# FINAL_PROJECT.net
KiCad netlist of a schematic drawn in EAGLE
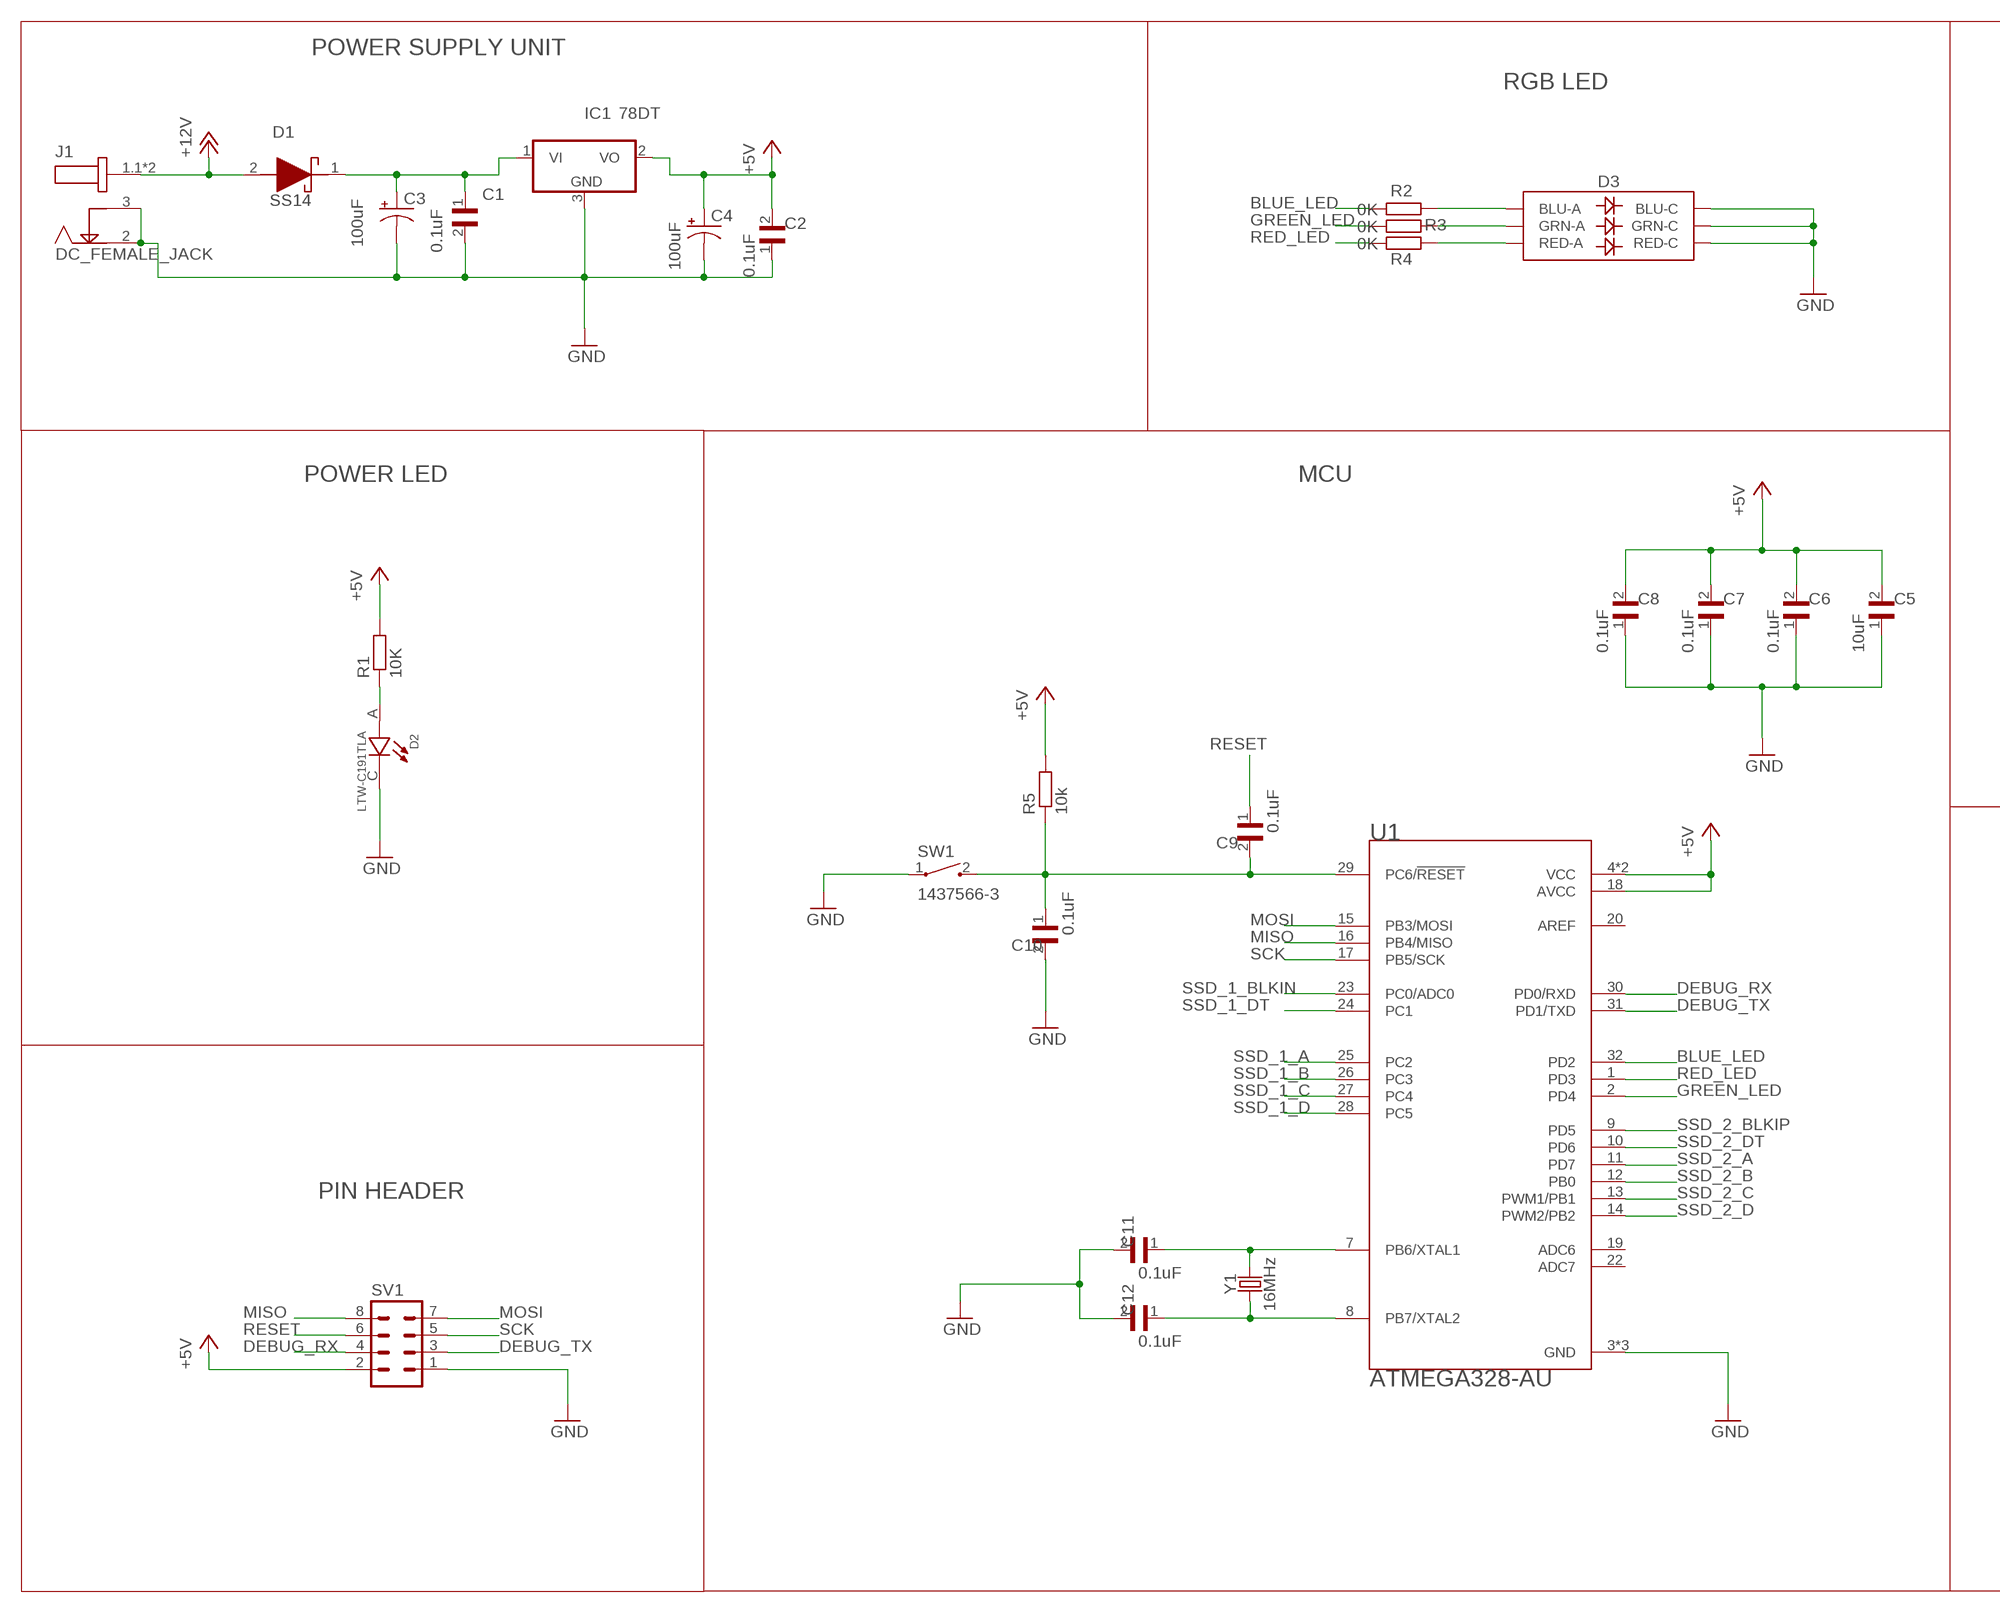
[diagram p0: schematic, sheet 1, part 1 of 2]
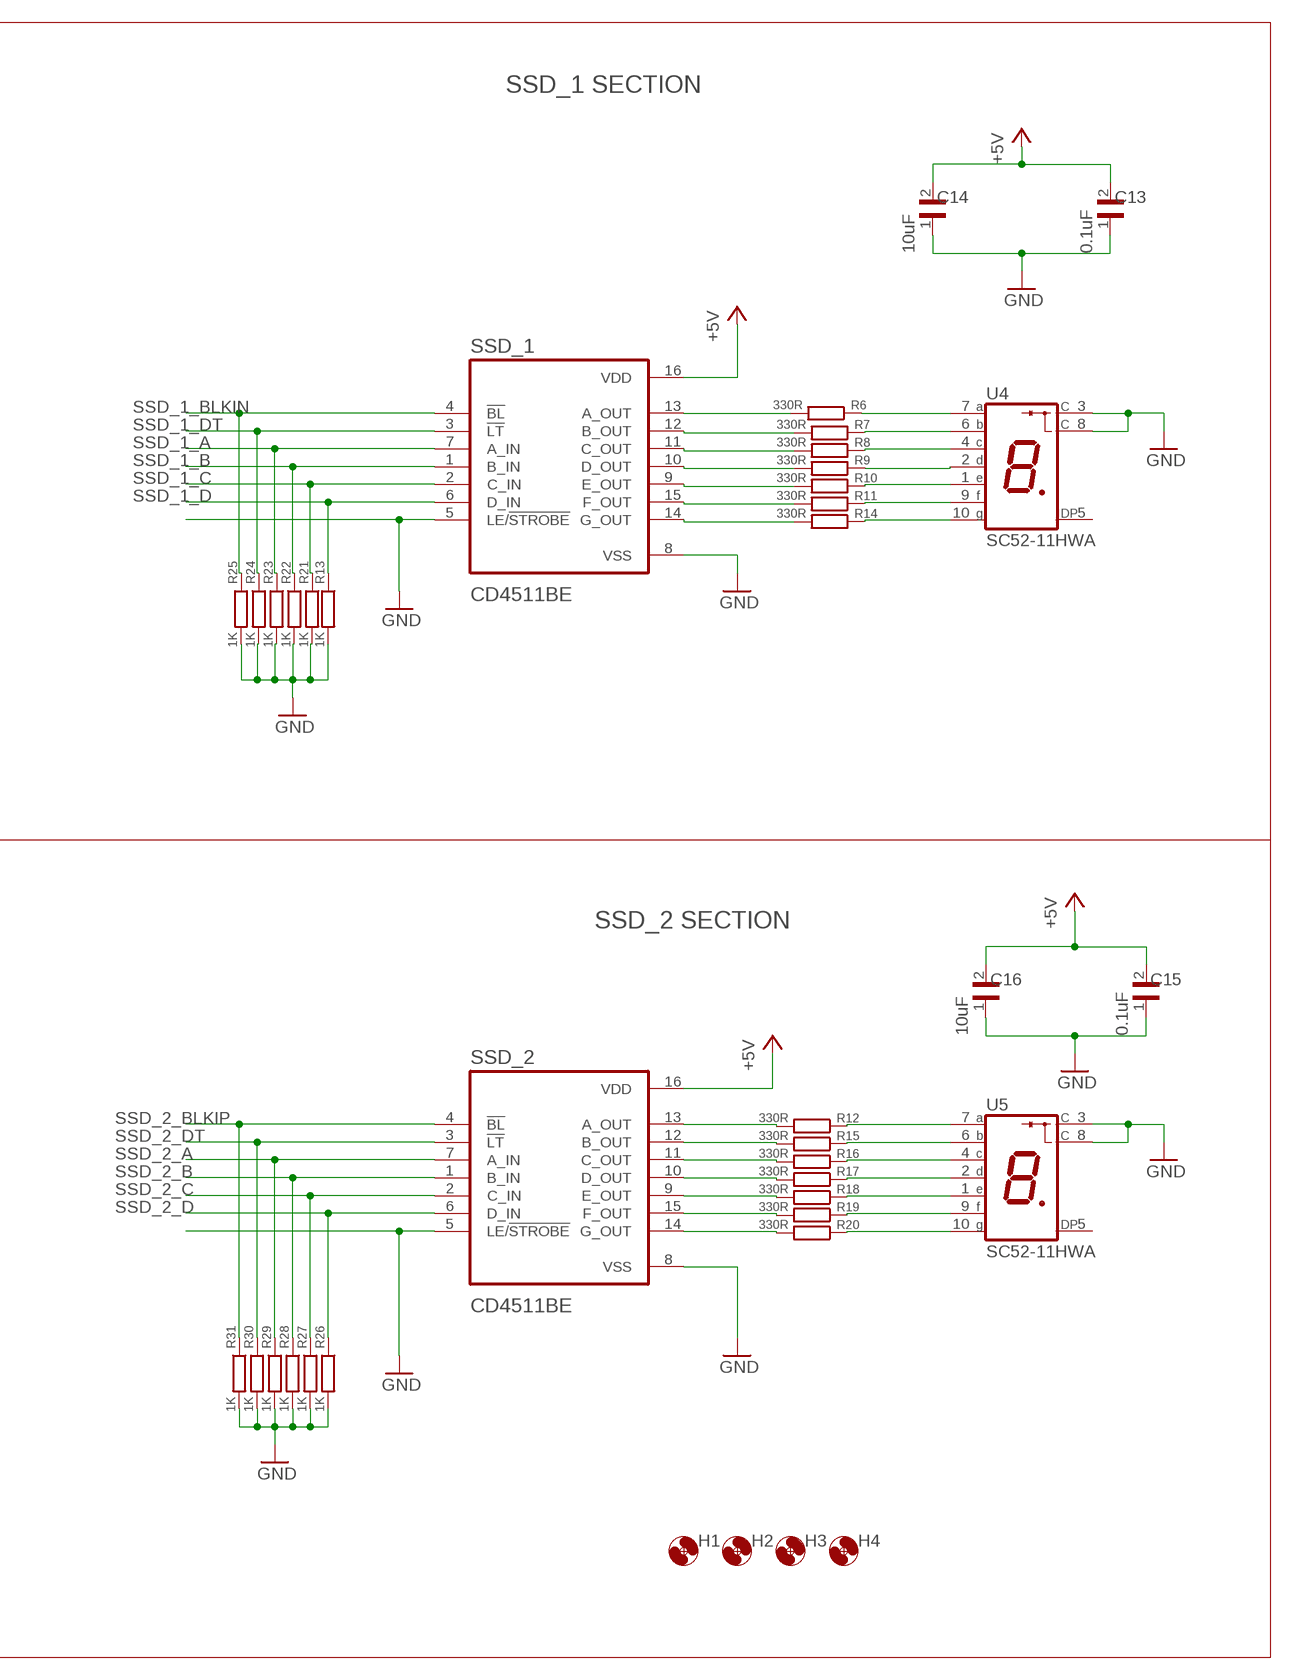
[diagram p1: schematic, sheet 1, part 2 of 2]

(export (version "E")
  (design (tool "Eeschema 10.0.6"))
  (components
    (comp (ref "C1")
      (value "0.1uF")
      (footprint "eagle-import:C0603")
      (fields (field (name "MF") "TDK") (field (name "MP") "CGA3E2X7R1H104K080AA"))
      (libsource (lib "eagle-import") (part "CAPACITOR"))
    )
    (comp (ref "C2")
      (value "0.1uF")
      (footprint "eagle-import:C0603")
      (fields
        (field (name "MF") "TDK")
        (field (name "MP") "CGA3E2X7R1H104K080AA")
        (field (name "SPICEPREFIX") "C")
      )
      (libsource (lib "eagle-import") (part "CAPACITOR"))
    )
    (comp (ref "C3")
      (value "100uF")
      (footprint "eagle-import:CPOL-RADIAL-2.5MM-6.5MM")
      (libsource (lib "eagle-import") (part "100UF-POLAR-RADIAL-2.5MM-25V-20%"))
    )
    (comp (ref "C4")
      (value "100uF")
      (footprint "eagle-import:CPOL-RADIAL-2.5MM-6.5MM")
      (libsource (lib "eagle-import") (part "100UF-POLAR-RADIAL-2.5MM-25V-20%"))
    )
    (comp (ref "C5")
      (value "10uF")
      (footprint "eagle-import:C0603")
      (fields
        (field (name "MF") "TDK")
        (field (name "MP") "CGA3E2X7R1H104K080AA")
        (field (name "SPICEPREFIX") "C")
      )
      (libsource (lib "eagle-import") (part "CAPACITOR"))
    )
    (comp (ref "C6")
      (value "0.1uF")
      (footprint "eagle-import:C0603")
      (fields
        (field (name "MF") "TDK")
        (field (name "MP") "CGA3E2X7R1H104K080AA")
        (field (name "SPICEPREFIX") "C")
      )
      (libsource (lib "eagle-import") (part "CAPACITOR"))
    )
    (comp (ref "C7")
      (value "0.1uF")
      (footprint "eagle-import:C0603")
      (fields
        (field (name "MF") "TDK")
        (field (name "MP") "CGA3E2X7R1H104K080AA")
        (field (name "SPICEPREFIX") "C")
      )
      (libsource (lib "eagle-import") (part "CAPACITOR"))
    )
    (comp (ref "C8")
      (value "0.1uF")
      (footprint "eagle-import:C0603")
      (fields
        (field (name "MF") "TDK")
        (field (name "MP") "CGA3E2X7R1H104K080AA")
        (field (name "SPICEPREFIX") "C")
      )
      (libsource (lib "eagle-import") (part "CAPACITOR"))
    )
    (comp (ref "C9")
      (value "0.1uF")
      (footprint "eagle-import:C0603")
      (fields
        (field (name "MF") "TDK")
        (field (name "MP") "CGA3E2X7R1H104K080AA")
        (field (name "SPICEPREFIX") "C")
      )
      (libsource (lib "eagle-import") (part "CAPACITOR"))
    )
    (comp (ref "C10")
      (value "0.1uF")
      (footprint "eagle-import:C0603")
      (fields
        (field (name "MF") "TDK")
        (field (name "MP") "CGA3E2X7R1H104K080AA")
        (field (name "SPICEPREFIX") "C")
      )
      (libsource (lib "eagle-import") (part "CAPACITOR"))
    )
    (comp (ref "C11")
      (value "0.1uF")
      (footprint "eagle-import:C0603")
      (fields
        (field (name "MF") "TDK")
        (field (name "MP") "CGA3E2X7R1H104K080AA")
        (field (name "SPICEPREFIX") "C")
      )
      (libsource (lib "eagle-import") (part "CAPACITOR"))
    )
    (comp (ref "C12")
      (value "0.1uF")
      (footprint "eagle-import:C0603")
      (fields
        (field (name "MF") "TDK")
        (field (name "MP") "CGA3E2X7R1H104K080AA")
        (field (name "SPICEPREFIX") "C")
      )
      (libsource (lib "eagle-import") (part "CAPACITOR"))
    )
    (comp (ref "C13")
      (value "0.1uF")
      (footprint "eagle-import:C0603")
      (fields
        (field (name "MF") "TDK")
        (field (name "MP") "CGA3E2X7R1H104K080AA")
        (field (name "SPICEPREFIX") "C")
      )
      (libsource (lib "eagle-import") (part "CAPACITOR"))
    )
    (comp (ref "C14")
      (value "10uF")
      (footprint "eagle-import:C0603")
      (fields
        (field (name "MF") "TDK")
        (field (name "MP") "CGA3E2X7R1H104K080AA")
        (field (name "SPICEPREFIX") "C")
      )
      (libsource (lib "eagle-import") (part "CAPACITOR"))
    )
    (comp (ref "C15")
      (value "0.1uF")
      (footprint "eagle-import:C0603")
      (fields
        (field (name "MF") "TDK")
        (field (name "MP") "CGA3E2X7R1H104K080AA")
        (field (name "SPICEPREFIX") "C")
      )
      (libsource (lib "eagle-import") (part "CAPACITOR"))
    )
    (comp (ref "C16")
      (value "10uF")
      (footprint "eagle-import:C0603")
      (fields
        (field (name "MF") "TDK")
        (field (name "MP") "CGA3E2X7R1H104K080AA")
        (field (name "SPICEPREFIX") "C")
      )
      (libsource (lib "eagle-import") (part "CAPACITOR"))
    )
    (comp (ref "D1")
      (value "SS14")
      (footprint "eagle-import:DIOM5126X250N")
      (fields (field (name "MOUSER_PART_NUMBER") "821-SS14"))
      (libsource (lib "eagle-import") (part "SS14"))
    )
    (comp (ref "D2")
      (value "LTW-C191TLA")
      (footprint "eagle-import:LEDC1608X65N")
      (fields (field (name "MF") "Lite-On"))
      (libsource (lib "eagle-import") (part "LTW-C191TLA"))
    )
    (comp (ref "D3")
      (value "LED-RGBNO_IC")
      (footprint "eagle-import:LED-TRICOLOR-5050")
      (libsource (lib "eagle-import") (part "LED-RGBNO_IC"))
    )
    (comp (ref "H1")
      (value "MOUNT-HOLE2.8")
      (footprint "eagle-import:2,8")
      (libsource (lib "eagle-import") (part "MOUNT-HOLE2.8"))
    )
    (comp (ref "H2")
      (value "MOUNT-HOLE2.8")
      (footprint "eagle-import:2,8")
      (libsource (lib "eagle-import") (part "MOUNT-HOLE2.8"))
    )
    (comp (ref "H3")
      (value "MOUNT-HOLE2.8")
      (footprint "eagle-import:2,8")
      (libsource (lib "eagle-import") (part "MOUNT-HOLE2.8"))
    )
    (comp (ref "H4")
      (value "MOUNT-HOLE2.8")
      (footprint "eagle-import:2,8")
      (libsource (lib "eagle-import") (part "MOUNT-HOLE2.8"))
    )
    (comp (ref "IC1")
      (value "78DT")
      (footprint "eagle-import:TO252")
      (libsource (lib "eagle-import") (part "78DT"))
    )
    (comp (ref "J1")
      (value "DC_FEMALE_JACK")
      (footprint "eagle-import:GCT_DCJ200-05-A-XX-X_REVA")
      (fields (field (name "MF") "Global Connector Technology") (field (name "MP") "DCJ200-05-A-K1-A"))
      (libsource (lib "eagle-import") (part "DCJ200-05-A-XX-X_REVA"))
    )
    (comp (ref "R1")
      (value "10K")
      (footprint "eagle-import:R0603")
      (fields (field (name "MF") "Yageo"))
      (libsource (lib "eagle-import") (part "RESISTOR"))
    )
    (comp (ref "R2")
      (value "0K")
      (footprint "eagle-import:R0603")
      (fields (field (name "MF") "Yageo"))
      (libsource (lib "eagle-import") (part "RESISTOR"))
    )
    (comp (ref "R3")
      (value "0K")
      (footprint "eagle-import:R0603")
      (fields (field (name "MF") "Yageo"))
      (libsource (lib "eagle-import") (part "RESISTOR"))
    )
    (comp (ref "R4")
      (value "0K")
      (footprint "eagle-import:R0603")
      (fields (field (name "MF") "Yageo"))
      (libsource (lib "eagle-import") (part "RESISTOR"))
    )
    (comp (ref "R5")
      (value "10k")
      (footprint "eagle-import:R0603")
      (fields (field (name "MF") "Yageo"))
      (libsource (lib "eagle-import") (part "RESISTOR"))
    )
    (comp (ref "R6")
      (value "330R")
      (footprint "eagle-import:R0603")
      (fields (field (name "MF") "Yageo"))
      (libsource (lib "eagle-import") (part "RESISTOR"))
    )
    (comp (ref "R7")
      (value "330R")
      (footprint "eagle-import:R0603")
      (fields (field (name "MF") "Yageo"))
      (libsource (lib "eagle-import") (part "RESISTOR"))
    )
    (comp (ref "R8")
      (value "330R")
      (footprint "eagle-import:R0603")
      (fields (field (name "MF") "Yageo"))
      (libsource (lib "eagle-import") (part "RESISTOR"))
    )
    (comp (ref "R9")
      (value "330R")
      (footprint "eagle-import:R0603")
      (fields (field (name "MF") "Yageo"))
      (libsource (lib "eagle-import") (part "RESISTOR"))
    )
    (comp (ref "R10")
      (value "330R")
      (footprint "eagle-import:R0603")
      (fields (field (name "MF") "Yageo"))
      (libsource (lib "eagle-import") (part "RESISTOR"))
    )
    (comp (ref "R11")
      (value "330R")
      (footprint "eagle-import:R0603")
      (fields (field (name "MF") "Yageo"))
      (libsource (lib "eagle-import") (part "RESISTOR"))
    )
    (comp (ref "R12")
      (value "330R")
      (footprint "eagle-import:R0603")
      (fields (field (name "MF") "Yageo"))
      (libsource (lib "eagle-import") (part "RESISTOR"))
    )
    (comp (ref "R13")
      (value "1K")
      (footprint "eagle-import:R0603")
      (fields (field (name "MF") "Yageo"))
      (libsource (lib "eagle-import") (part "RESISTOR"))
    )
    (comp (ref "R14")
      (value "330R")
      (footprint "eagle-import:R0603")
      (fields (field (name "MF") "Yageo"))
      (libsource (lib "eagle-import") (part "RESISTOR"))
    )
    (comp (ref "R15")
      (value "330R")
      (footprint "eagle-import:R0603")
      (fields (field (name "MF") "Yageo"))
      (libsource (lib "eagle-import") (part "RESISTOR"))
    )
    (comp (ref "R16")
      (value "330R")
      (footprint "eagle-import:R0603")
      (fields (field (name "MF") "Yageo"))
      (libsource (lib "eagle-import") (part "RESISTOR"))
    )
    (comp (ref "R17")
      (value "330R")
      (footprint "eagle-import:R0603")
      (fields (field (name "MF") "Yageo"))
      (libsource (lib "eagle-import") (part "RESISTOR"))
    )
    (comp (ref "R18")
      (value "330R")
      (footprint "eagle-import:R0603")
      (fields (field (name "MF") "Yageo"))
      (libsource (lib "eagle-import") (part "RESISTOR"))
    )
    (comp (ref "R19")
      (value "330R")
      (footprint "eagle-import:R0603")
      (fields (field (name "MF") "Yageo"))
      (libsource (lib "eagle-import") (part "RESISTOR"))
    )
    (comp (ref "R20")
      (value "330R")
      (footprint "eagle-import:R0603")
      (fields (field (name "MF") "Yageo"))
      (libsource (lib "eagle-import") (part "RESISTOR"))
    )
    (comp (ref "R21")
      (value "1K")
      (footprint "eagle-import:R0603")
      (fields (field (name "MF") "Yageo"))
      (libsource (lib "eagle-import") (part "RESISTOR"))
    )
    (comp (ref "R22")
      (value "1K")
      (footprint "eagle-import:R0603")
      (fields (field (name "MF") "Yageo"))
      (libsource (lib "eagle-import") (part "RESISTOR"))
    )
    (comp (ref "R23")
      (value "1K")
      (footprint "eagle-import:R0603")
      (fields (field (name "MF") "Yageo"))
      (libsource (lib "eagle-import") (part "RESISTOR"))
    )
    (comp (ref "R24")
      (value "1K")
      (footprint "eagle-import:R0603")
      (fields (field (name "MF") "Yageo"))
      (libsource (lib "eagle-import") (part "RESISTOR"))
    )
    (comp (ref "R25")
      (value "1K")
      (footprint "eagle-import:R0603")
      (fields (field (name "MF") "Yageo"))
      (libsource (lib "eagle-import") (part "RESISTOR"))
    )
    (comp (ref "R26")
      (value "1K")
      (footprint "eagle-import:R0603")
      (fields (field (name "MF") "Yageo"))
      (libsource (lib "eagle-import") (part "RESISTOR"))
    )
    (comp (ref "R27")
      (value "1K")
      (footprint "eagle-import:R0603")
      (fields (field (name "MF") "Yageo"))
      (libsource (lib "eagle-import") (part "RESISTOR"))
    )
    (comp (ref "R28")
      (value "1K")
      (footprint "eagle-import:R0603")
      (fields (field (name "MF") "Yageo"))
      (libsource (lib "eagle-import") (part "RESISTOR"))
    )
    (comp (ref "R29")
      (value "1K")
      (footprint "eagle-import:R0603")
      (fields (field (name "MF") "Yageo"))
      (libsource (lib "eagle-import") (part "RESISTOR"))
    )
    (comp (ref "R30")
      (value "1K")
      (footprint "eagle-import:R0603")
      (fields (field (name "MF") "Yageo"))
      (libsource (lib "eagle-import") (part "RESISTOR"))
    )
    (comp (ref "R31")
      (value "1K")
      (footprint "eagle-import:R0603")
      (fields (field (name "MF") "Yageo"))
      (libsource (lib "eagle-import") (part "RESISTOR"))
    )
    (comp (ref "SSD_1")
      (value "CD4511BE")
      (footprint "eagle-import:DIP794W45P254L1969H508Q16")
      (fields (field (name "MF") "Texas Instruments"))
      (libsource (lib "eagle-import") (part "CD4511BE"))
    )
    (comp (ref "SSD_2")
      (value "CD4511BE")
      (footprint "eagle-import:DIP794W45P254L1969H508Q16")
      (fields (field (name "MF") "Texas Instruments"))
      (libsource (lib "eagle-import") (part "CD4511BE"))
    )
    (comp (ref "SV1")
      (value "MA04-2")
      (footprint "eagle-import:MA04-2")
      (libsource (lib "eagle-import") (part "MA04-2"))
    )
    (comp (ref "SW1")
      (value "1437566-3")
      (footprint "eagle-import:SW_1437566-3")
      (fields (field (name "MF") "TE Connectivity"))
      (libsource (lib "eagle-import") (part "1437566-3"))
    )
    (comp (ref "U1")
      (value "ATMEGA328-AU")
      (footprint "eagle-import:QFP80P900X900X120-32N")
      (fields (field (name "MF") "Microchip"))
      (libsource (lib "eagle-import") (part "ATMEGA328-AU"))
    )
    (comp (ref "U4")
      (value "SC52-11HWA")
      (footprint "eagle-import:LED_SC52-11HWA")
      (fields (field (name "MF") "Kingbright"))
      (libsource (lib "eagle-import") (part "SC52-11HWA"))
    )
    (comp (ref "U5")
      (value "SC52-11HWA")
      (footprint "eagle-import:LED_SC52-11HWA")
      (fields (field (name "MF") "Kingbright"))
      (libsource (lib "eagle-import") (part "SC52-11HWA"))
    )
    (comp (ref "Y1")
      (value "16MHz")
      (footprint "eagle-import:HC49US")
      (libsource (lib "eagle-import") (part "CRYSTAL-16MHZPTH-HC49US"))
    )
  )
  (nets
    (net (code "1") (name "+5V") (class "Default")
      (node (ref "C13") (pin "2") (pinfunction "2_2") (pintype "passive"))
      (node (ref "C14") (pin "2") (pinfunction "2_2") (pintype "passive"))
      (node (ref "C15") (pin "2") (pinfunction "2_2") (pintype "passive"))
      (node (ref "C16") (pin "2") (pinfunction "2_2") (pintype "passive"))
      (node (ref "C2") (pin "2") (pinfunction "2_2") (pintype "passive"))
      (node (ref "C4") (pin "1") (pinfunction "+_1") (pintype "passive"))
      (node (ref "C5") (pin "2") (pinfunction "2_2") (pintype "passive"))
      (node (ref "C6") (pin "2") (pinfunction "2_2") (pintype "passive"))
      (node (ref "C7") (pin "2") (pinfunction "2_2") (pintype "passive"))
      (node (ref "C8") (pin "2") (pinfunction "2_2") (pintype "passive"))
      (node (ref "IC1") (pin "2") (pinfunction "VO_2") (pintype "passive"))
      (node (ref "R1") (pin "2") (pinfunction "2_2") (pintype "passive"))
      (node (ref "R5") (pin "2") (pinfunction "2_2") (pintype "passive"))
      (node (ref "SSD_1") (pin "16") (pinfunction "VDD_16") (pintype "power_in"))
      (node (ref "SSD_2") (pin "16") (pinfunction "VDD_16") (pintype "power_in"))
      (node (ref "SV1") (pin "2") (pinfunction "2_2") (pintype "passive"))
      (node (ref "U1") (pin "18") (pinfunction "AVCC_18") (pintype "power_in"))
      (node (ref "U1") (pin "4") (pinfunction "VCC_4") (pintype "power_in"))
      (node (ref "U1") (pin "6") (pinfunction "VCC_6") (pintype "power_in"))
    )
    (net (code "2") (name "+12V") (class "Default")
      (node (ref "D1") (pin "2") (pinfunction "A_2") (pintype "bidirectional"))
      (node (ref "J1") (pin "1.1") (pinfunction "1_1.1") (pintype "passive"))
      (node (ref "J1") (pin "1.2") (pinfunction "1_1.2") (pintype "passive"))
    )
    (net (code "3") (name "/BLUE_LED") (class "Default")
      (node (ref "R2") (pin "2") (pinfunction "2_2") (pintype "passive"))
      (node (ref "U1") (pin "32") (pinfunction "PD2_32") (pintype "bidirectional"))
    )
    (net (code "4") (name "/DEBUG_RX") (class "Default")
      (node (ref "SV1") (pin "4") (pinfunction "4_4") (pintype "passive"))
      (node (ref "U1") (pin "30") (pinfunction "PD0/RXD_30") (pintype "bidirectional"))
    )
    (net (code "5") (name "/DEBUG_TX") (class "Default")
      (node (ref "SV1") (pin "3") (pinfunction "3_3") (pintype "passive"))
      (node (ref "U1") (pin "31") (pinfunction "PD1/TXD_31") (pintype "bidirectional"))
    )
    (net (code "6") (name "/GREEN_LED") (class "Default")
      (node (ref "R3") (pin "2") (pinfunction "2_2") (pintype "passive"))
      (node (ref "U1") (pin "2") (pinfunction "PD4_2") (pintype "bidirectional"))
    )
    (net (code "7") (name "/MISO") (class "Default")
      (node (ref "SV1") (pin "8") (pinfunction "8_8") (pintype "passive"))
      (node (ref "U1") (pin "16") (pinfunction "PB4/MISO_16") (pintype "bidirectional"))
    )
    (net (code "8") (name "/MOSI") (class "Default")
      (node (ref "SV1") (pin "7") (pinfunction "7_7") (pintype "passive"))
      (node (ref "U1") (pin "15") (pinfunction "PB3/MOSI_15") (pintype "bidirectional"))
    )
    (net (code "9") (name "/RED_LED") (class "Default")
      (node (ref "R4") (pin "2") (pinfunction "2_2") (pintype "passive"))
      (node (ref "U1") (pin "1") (pinfunction "PD3_1") (pintype "bidirectional"))
    )
    (net (code "10") (name "/RESET") (class "Default")
      (node (ref "C9") (pin "1") (pinfunction "1_1") (pintype "passive"))
      (node (ref "SV1") (pin "6") (pinfunction "6_6") (pintype "passive"))
    )
    (net (code "11") (name "/SCK") (class "Default")
      (node (ref "SV1") (pin "5") (pinfunction "5_5") (pintype "passive"))
      (node (ref "U1") (pin "17") (pinfunction "PB5/SCK_17") (pintype "bidirectional"))
    )
    (net (code "12") (name "/SSD_1_A") (class "Default")
      (node (ref "R23") (pin "1") (pinfunction "1_1") (pintype "passive"))
      (node (ref "SSD_1") (pin "7") (pinfunction "A_IN_7") (pintype "input"))
      (node (ref "U1") (pin "25") (pinfunction "PC2_25") (pintype "bidirectional"))
    )
    (net (code "13") (name "/SSD_1_B") (class "Default")
      (node (ref "R22") (pin "1") (pinfunction "1_1") (pintype "passive"))
      (node (ref "SSD_1") (pin "1") (pinfunction "B_IN_1") (pintype "input"))
      (node (ref "U1") (pin "26") (pinfunction "PC3_26") (pintype "bidirectional"))
    )
    (net (code "14") (name "/SSD_1_BLKIN") (class "Default")
      (node (ref "R25") (pin "1") (pinfunction "1_1") (pintype "passive"))
      (node (ref "SSD_1") (pin "4") (pinfunction "~{BL}_4") (pintype "input"))
      (node (ref "U1") (pin "23") (pinfunction "PC0/ADC0_23") (pintype "bidirectional"))
    )
    (net (code "15") (name "/SSD_1_C") (class "Default")
      (node (ref "R21") (pin "1") (pinfunction "1_1") (pintype "passive"))
      (node (ref "SSD_1") (pin "2") (pinfunction "C_IN_2") (pintype "input"))
      (node (ref "U1") (pin "27") (pinfunction "PC4_27") (pintype "bidirectional"))
    )
    (net (code "16") (name "/SSD_1_D") (class "Default")
      (node (ref "R13") (pin "1") (pinfunction "1_1") (pintype "passive"))
      (node (ref "SSD_1") (pin "6") (pinfunction "D_IN_6") (pintype "input"))
      (node (ref "U1") (pin "28") (pinfunction "PC5_28") (pintype "bidirectional"))
    )
    (net (code "17") (name "/SSD_1_DT") (class "Default")
      (node (ref "R24") (pin "1") (pinfunction "1_1") (pintype "passive"))
      (node (ref "SSD_1") (pin "3") (pinfunction "~{LT}_3") (pintype "input"))
      (node (ref "U1") (pin "24") (pinfunction "PC1_24") (pintype "bidirectional"))
    )
    (net (code "18") (name "/SSD_2_A") (class "Default")
      (node (ref "R29") (pin "1") (pinfunction "1_1") (pintype "passive"))
      (node (ref "SSD_2") (pin "7") (pinfunction "A_IN_7") (pintype "input"))
      (node (ref "U1") (pin "11") (pinfunction "PD7_11") (pintype "bidirectional"))
    )
    (net (code "19") (name "/SSD_2_B") (class "Default")
      (node (ref "R28") (pin "1") (pinfunction "1_1") (pintype "passive"))
      (node (ref "SSD_2") (pin "1") (pinfunction "B_IN_1") (pintype "input"))
      (node (ref "U1") (pin "12") (pinfunction "PB0_12") (pintype "bidirectional"))
    )
    (net (code "20") (name "/SSD_2_BLKIP") (class "Default")
      (node (ref "R31") (pin "1") (pinfunction "1_1") (pintype "passive"))
      (node (ref "SSD_2") (pin "4") (pinfunction "~{BL}_4") (pintype "input"))
      (node (ref "U1") (pin "9") (pinfunction "PD5_9") (pintype "bidirectional"))
    )
    (net (code "21") (name "/SSD_2_C") (class "Default")
      (node (ref "R27") (pin "1") (pinfunction "1_1") (pintype "passive"))
      (node (ref "SSD_2") (pin "2") (pinfunction "C_IN_2") (pintype "input"))
      (node (ref "U1") (pin "13") (pinfunction "PWM1/PB1_13") (pintype "bidirectional"))
    )
    (net (code "22") (name "/SSD_2_D") (class "Default")
      (node (ref "R26") (pin "1") (pinfunction "1_1") (pintype "passive"))
      (node (ref "SSD_2") (pin "6") (pinfunction "D_IN_6") (pintype "input"))
      (node (ref "U1") (pin "14") (pinfunction "PWM2/PB2_14") (pintype "bidirectional"))
    )
    (net (code "23") (name "/SSD_2_DT") (class "Default")
      (node (ref "R30") (pin "1") (pinfunction "1_1") (pintype "passive"))
      (node (ref "SSD_2") (pin "3") (pinfunction "~{LT}_3") (pintype "input"))
      (node (ref "U1") (pin "10") (pinfunction "PD6_10") (pintype "bidirectional"))
    )
    (net (code "24") (name "GND") (class "Default")
      (node (ref "C1") (pin "2") (pinfunction "2_2") (pintype "passive"))
      (node (ref "C10") (pin "2") (pinfunction "2_2") (pintype "passive"))
      (node (ref "C11") (pin "2") (pinfunction "2_2") (pintype "passive"))
      (node (ref "C12") (pin "2") (pinfunction "2_2") (pintype "passive"))
      (node (ref "C13") (pin "1") (pinfunction "1_1") (pintype "passive"))
      (node (ref "C14") (pin "1") (pinfunction "1_1") (pintype "passive"))
      (node (ref "C15") (pin "1") (pinfunction "1_1") (pintype "passive"))
      (node (ref "C16") (pin "1") (pinfunction "1_1") (pintype "passive"))
      (node (ref "C2") (pin "1") (pinfunction "1_1") (pintype "passive"))
      (node (ref "C3") (pin "2") (pinfunction "-_2") (pintype "passive"))
      (node (ref "C4") (pin "2") (pinfunction "-_2") (pintype "passive"))
      (node (ref "C5") (pin "1") (pinfunction "1_1") (pintype "passive"))
      (node (ref "C6") (pin "1") (pinfunction "1_1") (pintype "passive"))
      (node (ref "C7") (pin "1") (pinfunction "1_1") (pintype "passive"))
      (node (ref "C8") (pin "1") (pinfunction "1_1") (pintype "passive"))
      (node (ref "D2") (pin "C") (pinfunction "C_C") (pintype "passive"))
      (node (ref "D3") (pin "4") (pinfunction "BLU-C_4") (pintype "bidirectional"))
      (node (ref "D3") (pin "5") (pinfunction "RED-C_5") (pintype "bidirectional"))
      (node (ref "D3") (pin "6") (pinfunction "GRN-C_6") (pintype "bidirectional"))
      (node (ref "IC1") (pin "3") (pinfunction "GND_3") (pintype "passive"))
      (node (ref "J1") (pin "2") (pinfunction "2_2") (pintype "passive"))
      (node (ref "J1") (pin "3") (pinfunction "3_3") (pintype "passive"))
      (node (ref "R13") (pin "2") (pinfunction "2_2") (pintype "passive"))
      (node (ref "R21") (pin "2") (pinfunction "2_2") (pintype "passive"))
      (node (ref "R22") (pin "2") (pinfunction "2_2") (pintype "passive"))
      (node (ref "R23") (pin "2") (pinfunction "2_2") (pintype "passive"))
      (node (ref "R24") (pin "2") (pinfunction "2_2") (pintype "passive"))
      (node (ref "R25") (pin "2") (pinfunction "2_2") (pintype "passive"))
      (node (ref "R26") (pin "2") (pinfunction "2_2") (pintype "passive"))
      (node (ref "R27") (pin "2") (pinfunction "2_2") (pintype "passive"))
      (node (ref "R28") (pin "2") (pinfunction "2_2") (pintype "passive"))
      (node (ref "R29") (pin "2") (pinfunction "2_2") (pintype "passive"))
      (node (ref "R30") (pin "2") (pinfunction "2_2") (pintype "passive"))
      (node (ref "R31") (pin "2") (pinfunction "2_2") (pintype "passive"))
      (node (ref "SSD_1") (pin "5") (pinfunction "LE/~{STROBE}_5") (pintype "input"))
      (node (ref "SSD_1") (pin "8") (pinfunction "VSS_8") (pintype "power_in"))
      (node (ref "SSD_2") (pin "5") (pinfunction "LE/~{STROBE}_5") (pintype "input"))
      (node (ref "SSD_2") (pin "8") (pinfunction "VSS_8") (pintype "power_in"))
      (node (ref "SV1") (pin "1") (pinfunction "1_1") (pintype "passive"))
      (node (ref "SW1") (pin "1") (pinfunction "1_1") (pintype "passive"))
      (node (ref "U1") (pin "21") (pinfunction "GND_21") (pintype "power_in"))
      (node (ref "U1") (pin "3") (pinfunction "GND_3") (pintype "power_in"))
      (node (ref "U1") (pin "5") (pinfunction "GND_5") (pintype "power_in"))
      (node (ref "U4") (pin "3") (pinfunction "C_3") (pintype "passive"))
      (node (ref "U4") (pin "8") (pinfunction "C_8") (pintype "passive"))
      (node (ref "U5") (pin "3") (pinfunction "C_3") (pintype "passive"))
      (node (ref "U5") (pin "8") (pinfunction "C_8") (pintype "passive"))
    )
    (net (code "25") (name "Net-(C3-+)") (class "Default")
      (node (ref "C1") (pin "1") (pinfunction "1_1") (pintype "passive"))
      (node (ref "C3") (pin "1") (pinfunction "+_1") (pintype "passive"))
      (node (ref "D1") (pin "1") (pinfunction "K_1") (pintype "bidirectional"))
      (node (ref "IC1") (pin "1") (pinfunction "VI_1") (pintype "input"))
    )
    (net (code "26") (name "Net-(D2-PadA)") (class "Default")
      (node (ref "D2") (pin "A") (pinfunction "A_A") (pintype "passive"))
      (node (ref "R1") (pin "1") (pinfunction "1_1") (pintype "passive"))
    )
    (net (code "27") (name "Net-(D3-BLU-A)") (class "Default")
      (node (ref "D3") (pin "3") (pinfunction "BLU-A_3") (pintype "bidirectional"))
      (node (ref "R2") (pin "1") (pinfunction "1_1") (pintype "passive"))
    )
    (net (code "28") (name "Net-(D3-GRN-A)") (class "Default")
      (node (ref "D3") (pin "1") (pinfunction "GRN-A_1") (pintype "bidirectional"))
      (node (ref "R3") (pin "1") (pinfunction "1_1") (pintype "passive"))
    )
    (net (code "29") (name "Net-(D3-RED-A)") (class "Default")
      (node (ref "D3") (pin "2") (pinfunction "RED-A_2") (pintype "bidirectional"))
      (node (ref "R4") (pin "1") (pinfunction "1_1") (pintype "passive"))
    )
    (net (code "30") (name "Net-(R8-Pad1)") (class "Default")
      (node (ref "R8") (pin "1") (pinfunction "1_1") (pintype "passive"))
      (node (ref "U4") (pin "4") (pinfunction "C_4") (pintype "passive"))
    )
    (net (code "31") (name "Net-(R16-Pad1)") (class "Default")
      (node (ref "R16") (pin "1") (pinfunction "1_1") (pintype "passive"))
      (node (ref "U5") (pin "4") (pinfunction "C_4") (pintype "passive"))
    )
    (net (code "32") (name "Net-(SSD_1-A_OUT)") (class "Default")
      (node (ref "R6") (pin "2") (pinfunction "2_2") (pintype "passive"))
      (node (ref "SSD_1") (pin "13") (pinfunction "A_OUT_13") (pintype "output"))
    )
    (net (code "33") (name "Net-(SSD_1-B_OUT)") (class "Default")
      (node (ref "R7") (pin "2") (pinfunction "2_2") (pintype "passive"))
      (node (ref "SSD_1") (pin "12") (pinfunction "B_OUT_12") (pintype "output"))
    )
    (net (code "34") (name "Net-(SSD_1-C_OUT)") (class "Default")
      (node (ref "R8") (pin "2") (pinfunction "2_2") (pintype "passive"))
      (node (ref "SSD_1") (pin "11") (pinfunction "C_OUT_11") (pintype "output"))
    )
    (net (code "35") (name "Net-(SSD_1-D_OUT)") (class "Default")
      (node (ref "R9") (pin "2") (pinfunction "2_2") (pintype "passive"))
      (node (ref "SSD_1") (pin "10") (pinfunction "D_OUT_10") (pintype "output"))
    )
    (net (code "36") (name "Net-(SSD_1-E_OUT)") (class "Default")
      (node (ref "R10") (pin "2") (pinfunction "2_2") (pintype "passive"))
      (node (ref "SSD_1") (pin "9") (pinfunction "E_OUT_9") (pintype "output"))
    )
    (net (code "37") (name "Net-(SSD_1-F_OUT)") (class "Default")
      (node (ref "R11") (pin "2") (pinfunction "2_2") (pintype "passive"))
      (node (ref "SSD_1") (pin "15") (pinfunction "F_OUT_15") (pintype "output"))
    )
    (net (code "38") (name "Net-(SSD_1-G_OUT)") (class "Default")
      (node (ref "R14") (pin "2") (pinfunction "2_2") (pintype "passive"))
      (node (ref "SSD_1") (pin "14") (pinfunction "G_OUT_14") (pintype "output"))
    )
    (net (code "39") (name "Net-(SSD_2-A_OUT)") (class "Default")
      (node (ref "R12") (pin "2") (pinfunction "2_2") (pintype "passive"))
      (node (ref "SSD_2") (pin "13") (pinfunction "A_OUT_13") (pintype "output"))
    )
    (net (code "40") (name "Net-(SSD_2-B_OUT)") (class "Default")
      (node (ref "R15") (pin "2") (pinfunction "2_2") (pintype "passive"))
      (node (ref "SSD_2") (pin "12") (pinfunction "B_OUT_12") (pintype "output"))
    )
    (net (code "41") (name "Net-(SSD_2-C_OUT)") (class "Default")
      (node (ref "R16") (pin "2") (pinfunction "2_2") (pintype "passive"))
      (node (ref "SSD_2") (pin "11") (pinfunction "C_OUT_11") (pintype "output"))
    )
    (net (code "42") (name "Net-(SSD_2-D_OUT)") (class "Default")
      (node (ref "R17") (pin "2") (pinfunction "2_2") (pintype "passive"))
      (node (ref "SSD_2") (pin "10") (pinfunction "D_OUT_10") (pintype "output"))
    )
    (net (code "43") (name "Net-(SSD_2-E_OUT)") (class "Default")
      (node (ref "R18") (pin "2") (pinfunction "2_2") (pintype "passive"))
      (node (ref "SSD_2") (pin "9") (pinfunction "E_OUT_9") (pintype "output"))
    )
    (net (code "44") (name "Net-(SSD_2-F_OUT)") (class "Default")
      (node (ref "R19") (pin "2") (pinfunction "2_2") (pintype "passive"))
      (node (ref "SSD_2") (pin "15") (pinfunction "F_OUT_15") (pintype "output"))
    )
    (net (code "45") (name "Net-(SSD_2-G_OUT)") (class "Default")
      (node (ref "R20") (pin "2") (pinfunction "2_2") (pintype "passive"))
      (node (ref "SSD_2") (pin "14") (pinfunction "G_OUT_14") (pintype "output"))
    )
    (net (code "46") (name "Net-(U1-PB6{slash}XTAL1)") (class "Default")
      (node (ref "C11") (pin "1") (pinfunction "1_1") (pintype "passive"))
      (node (ref "U1") (pin "7") (pinfunction "PB6/XTAL1_7") (pintype "bidirectional"))
      (node (ref "Y1") (pin "2") (pinfunction "2_2") (pintype "passive"))
    )
    (net (code "47") (name "Net-(U1-PB7{slash}XTAL2)") (class "Default")
      (node (ref "C12") (pin "1") (pinfunction "1_1") (pintype "passive"))
      (node (ref "U1") (pin "8") (pinfunction "PB7/XTAL2_8") (pintype "bidirectional"))
      (node (ref "Y1") (pin "1") (pinfunction "1_1") (pintype "passive"))
    )
    (net (code "48") (name "Net-(U1-PC6{slash}~{RESET})") (class "Default")
      (node (ref "C10") (pin "1") (pinfunction "1_1") (pintype "passive"))
      (node (ref "C9") (pin "2") (pinfunction "2_2") (pintype "passive"))
      (node (ref "R5") (pin "1") (pinfunction "1_1") (pintype "passive"))
      (node (ref "SW1") (pin "2") (pinfunction "2_2") (pintype "passive"))
      (node (ref "U1") (pin "29") (pinfunction "PC6/~{RESET}_29") (pintype "bidirectional"))
    )
    (net (code "49") (name "Net-(U4-A)") (class "Default")
      (node (ref "R6") (pin "1") (pinfunction "1_1") (pintype "passive"))
      (node (ref "U4") (pin "7") (pinfunction "A_7") (pintype "passive"))
    )
    (net (code "50") (name "Net-(U4-B)") (class "Default")
      (node (ref "R7") (pin "1") (pinfunction "1_1") (pintype "passive"))
      (node (ref "U4") (pin "6") (pinfunction "B_6") (pintype "passive"))
    )
    (net (code "51") (name "Net-(U4-D)") (class "Default")
      (node (ref "R9") (pin "1") (pinfunction "1_1") (pintype "passive"))
      (node (ref "U4") (pin "2") (pinfunction "D_2") (pintype "passive"))
    )
    (net (code "52") (name "Net-(U4-E)") (class "Default")
      (node (ref "R10") (pin "1") (pinfunction "1_1") (pintype "passive"))
      (node (ref "U4") (pin "1") (pinfunction "E_1") (pintype "passive"))
    )
    (net (code "53") (name "Net-(U4-F)") (class "Default")
      (node (ref "R11") (pin "1") (pinfunction "1_1") (pintype "passive"))
      (node (ref "U4") (pin "9") (pinfunction "F_9") (pintype "passive"))
    )
    (net (code "54") (name "Net-(U4-G)") (class "Default")
      (node (ref "R14") (pin "1") (pinfunction "1_1") (pintype "passive"))
      (node (ref "U4") (pin "10") (pinfunction "G_10") (pintype "passive"))
    )
    (net (code "55") (name "Net-(U5-A)") (class "Default")
      (node (ref "R12") (pin "1") (pinfunction "1_1") (pintype "passive"))
      (node (ref "U5") (pin "7") (pinfunction "A_7") (pintype "passive"))
    )
    (net (code "56") (name "Net-(U5-B)") (class "Default")
      (node (ref "R15") (pin "1") (pinfunction "1_1") (pintype "passive"))
      (node (ref "U5") (pin "6") (pinfunction "B_6") (pintype "passive"))
    )
    (net (code "57") (name "Net-(U5-D)") (class "Default")
      (node (ref "R17") (pin "1") (pinfunction "1_1") (pintype "passive"))
      (node (ref "U5") (pin "2") (pinfunction "D_2") (pintype "passive"))
    )
    (net (code "58") (name "Net-(U5-E)") (class "Default")
      (node (ref "R18") (pin "1") (pinfunction "1_1") (pintype "passive"))
      (node (ref "U5") (pin "1") (pinfunction "E_1") (pintype "passive"))
    )
    (net (code "59") (name "Net-(U5-F)") (class "Default")
      (node (ref "R19") (pin "1") (pinfunction "1_1") (pintype "passive"))
      (node (ref "U5") (pin "9") (pinfunction "F_9") (pintype "passive"))
    )
    (net (code "60") (name "Net-(U5-G)") (class "Default")
      (node (ref "R20") (pin "1") (pinfunction "1_1") (pintype "passive"))
      (node (ref "U5") (pin "10") (pinfunction "G_10") (pintype "passive"))
    )
    (net (code "61") (name "unconnected-(U1-ADC6-Pad19)") (class "Default")
      (node (ref "U1") (pin "19") (pinfunction "ADC6_19") (pintype "bidirectional"))
    )
    (net (code "62") (name "unconnected-(U1-ADC7-Pad22)") (class "Default")
      (node (ref "U1") (pin "22") (pinfunction "ADC7_22") (pintype "bidirectional"))
    )
    (net (code "63") (name "unconnected-(U1-AREF-Pad20)") (class "Default")
      (node (ref "U1") (pin "20") (pinfunction "AREF_20") (pintype "input"))
    )
    (net (code "64") (name "unconnected-(U4-DP-Pad5)") (class "Default")
      (node (ref "U4") (pin "5") (pinfunction "DP_5") (pintype "passive"))
    )
    (net (code "65") (name "unconnected-(U5-DP-Pad5)") (class "Default")
      (node (ref "U5") (pin "5") (pinfunction "DP_5") (pintype "passive"))
    )
  )
)
